# SCH_MAX31865.net
KiCad netlist of a schematic drawn in Altium Designer
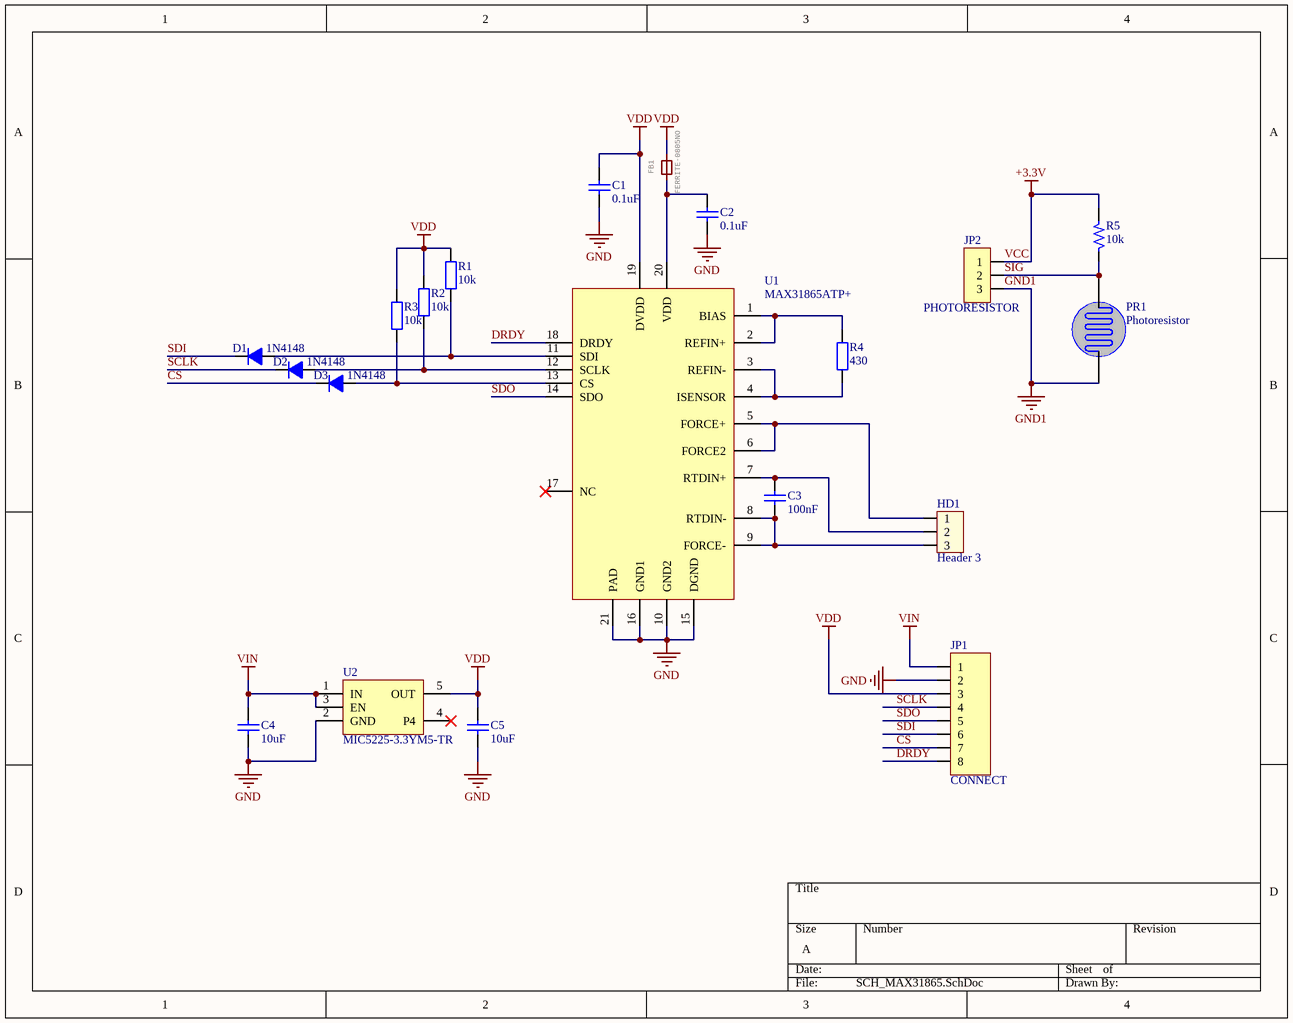
[diagram p0: SCH_MAX31865.SchDoc]

(export (version "E")
  (design (tool "Eeschema 10.0.6"))
  (components
    (comp (ref "C1")
      (value "0.1uF")
      (footprint "tu 0805")
      (description "SMD 0603")
      (libsource (lib "Altium_Lib_by_KhueNguyenCreator") (part "Tu 0805 101 50V 20%"))
    )
    (comp (ref "C2")
      (value "0.1uF")
      (footprint "tu 0805")
      (description "SMD 0603")
      (libsource (lib "Altium_Lib_by_KhueNguyenCreator") (part "Tu 0805 101 50V 20%"))
    )
    (comp (ref "C3")
      (value "100nF")
      (footprint "tu 0805")
      (description "SMD 0603")
      (libsource (lib "Altium_Lib_by_KhueNguyenCreator") (part "Tu 0805 101 50V 20%"))
    )
    (comp (ref "C4")
      (value "10uF")
      (footprint "tu 0805")
      (description "SMD 0603")
      (libsource (lib "Altium_Lib_by_KhueNguyenCreator") (part "Tu 0805 101 50V 20%"))
    )
    (comp (ref "C5")
      (value "10uF")
      (footprint "tu 0805")
      (description "SMD 0603")
      (libsource (lib "Altium_Lib_by_KhueNguyenCreator") (part "Tu 0805 101 50V 20%"))
    )
    (comp (ref "D1")
      (value "1N4148")
      (footprint "SOD523F")
      (description "Diode 1A SMD")
      (libsource (lib "My library altium") (part "Diode  1N4007"))
    )
    (comp (ref "D2")
      (value "1N4148")
      (footprint "SOD523F")
      (description "Diode 1A SMD")
      (libsource (lib "My library altium") (part "Diode  1N4007"))
    )
    (comp (ref "D3")
      (value "1N4148")
      (footprint "SOD523F")
      (description "Diode 1A SMD")
      (libsource (lib "My library altium") (part "Diode  1N4007"))
    )
    (comp (ref "FB1")
      (value "FERRITE-0805NO")
      (footprint "tu 0805")
      (libsource (lib "microbuilder") (part "FERRITE-0805NO"))
    )
    (comp (ref "HD1")
      (value "Header 3")
      (footprint "HED3")
      (description "jumper 1x3")
      (libsource (lib "My library altium") (part "Header 3"))
    )
    (comp (ref "JP1")
      (value "CONNECT")
      (footprint "JP 1x8 DT")
      (description "jumper 1x8")
      (libsource (lib "Altium_Lib_by_KhueNguyenCreator") (part "JP 1x8 2.54 Duc Thang"))
    )
    (comp (ref "JP2")
      (value "PHOTORESISTOR")
      (footprint "JP 1x3 DT")
      (description "Cắm")
      (libsource (lib "Altium_Lib_by_KhueNguyenCreator") (part "JP 1x3 2.54 Duc Thang"))
    )
    (comp (ref "PR1")
      (value "Photoresistor")
      (footprint "CDS")
      (fields (field (name "CREATOR") "Bien Nguyen"))
      (libsource (lib "My library altium") (part "Photoresistor"))
    )
    (comp (ref "R1")
      (value "10k")
      (footprint "tro smd 0805")
      (description "SMD 0603")
      (libsource (lib "Altium_Lib_by_KhueNguyenCreator") (part "Tro 0805 1% 18k"))
    )
    (comp (ref "R2")
      (value "10k")
      (footprint "tro smd 0805")
      (description "SMD 0603")
      (libsource (lib "Altium_Lib_by_KhueNguyenCreator") (part "Tro 0805 1% 18k"))
    )
    (comp (ref "R3")
      (value "10k")
      (footprint "tro smd 0805")
      (description "SMD 0603")
      (libsource (lib "Altium_Lib_by_KhueNguyenCreator") (part "Tro 0805 1% 18k"))
    )
    (comp (ref "R4")
      (value "430")
      (footprint "tro smd 0805")
      (description "SMD 0805")
      (libsource (lib "Altium_Lib_by_KhueNguyenCreator") (part "Tro 0805 1% 18k"))
    )
    (comp (ref "R5")
      (value "10k")
      (footprint "R1/4W")
      (description "Res cắm")
      (libsource (lib "My library altium") (part "Res"))
    )
    (comp (ref "U1")
      (value "MAX31865ATP+")
      (footprint "21-0140_T2055+5_MXM")
      (libsource (lib "MAX31865ATP&plus_plus_") (part "MAX31865ATP+"))
    )
    (comp (ref "U2")
      (value "MIC5225-3.3YM5-TR")
      (footprint "SOT-23-5_M5_MCH")
      (description "No Description Available")
      (libsource (lib "MIC5225-3P3YM5-TR") (part "MIC5225-3.3YM5-TR"))
    )
  )
  (nets
    (net (code "1") (name "+3.3V") (class "Default")
      (node (ref "JP2") (pin "1") (pinfunction "1_1") (pintype "passive"))
      (node (ref "R5") (pin "2") (pinfunction "2_2") (pintype "passive"))
    )
    (net (code "2") (name "/CS") (class "Default")
      (node (ref "D3") (pin "K") (pinfunction "K_K") (pintype "passive"))
      (node (ref "JP1") (pin "7") (pinfunction "7_7") (pintype "passive"))
    )
    (net (code "3") (name "/DRDY") (class "Default")
      (node (ref "JP1") (pin "8") (pinfunction "8_8") (pintype "passive"))
      (node (ref "U1") (pin "18") (pinfunction "DRDY_18") (pintype "passive"))
    )
    (net (code "4") (name "/SCLK") (class "Default")
      (node (ref "D2") (pin "K") (pinfunction "K_K") (pintype "passive"))
      (node (ref "JP1") (pin "4") (pinfunction "4_4") (pintype "passive"))
    )
    (net (code "5") (name "/SDI") (class "Default")
      (node (ref "D1") (pin "K") (pinfunction "K_K") (pintype "passive"))
      (node (ref "JP1") (pin "6") (pinfunction "6_6") (pintype "passive"))
    )
    (net (code "6") (name "/SDO") (class "Default")
      (node (ref "JP1") (pin "5") (pinfunction "5_5") (pintype "passive"))
      (node (ref "U1") (pin "14") (pinfunction "SDO_14") (pintype "passive"))
    )
    (net (code "7") (name "/SIG") (class "Default")
      (node (ref "JP2") (pin "2") (pinfunction "2_2") (pintype "passive"))
      (node (ref "PR1") (pin "2") (pinfunction "2_2") (pintype "passive"))
      (node (ref "R5") (pin "1") (pinfunction "1_1") (pintype "passive"))
    )
    (net (code "8") (name "GND") (class "Default")
      (node (ref "C1") (pin "2") (pinfunction "2_2") (pintype "passive"))
      (node (ref "C2") (pin "2") (pinfunction "2_2") (pintype "passive"))
      (node (ref "C4") (pin "2") (pinfunction "2_2") (pintype "passive"))
      (node (ref "C5") (pin "2") (pinfunction "2_2") (pintype "passive"))
      (node (ref "JP1") (pin "2") (pinfunction "2_2") (pintype "passive"))
      (node (ref "U1") (pin "10") (pinfunction "GND2_10") (pintype "power_in"))
      (node (ref "U1") (pin "15") (pinfunction "DGND_15") (pintype "power_in"))
      (node (ref "U1") (pin "16") (pinfunction "GND1_16") (pintype "power_in"))
      (node (ref "U1") (pin "21") (pinfunction "PAD_21") (pintype "power_in"))
      (node (ref "U2") (pin "2") (pinfunction "GND_2") (pintype "passive"))
    )
    (net (code "9") (name "GND1") (class "Default")
      (node (ref "JP2") (pin "3") (pinfunction "3_3") (pintype "passive"))
      (node (ref "PR1") (pin "1") (pinfunction "1_1") (pintype "passive"))
    )
    (net (code "10") (name "Net-(FB1-P$1)") (class "Default")
      (node (ref "C2") (pin "1") (pinfunction "1_1") (pintype "passive"))
      (node (ref "FB1") (pin "1") (pinfunction "P$1_1") (pintype "passive"))
      (node (ref "U1") (pin "20") (pinfunction "VDD_20") (pintype "power_in"))
    )
    (net (code "11") (name "Net-(U1-BIAS)") (class "Default")
      (node (ref "R4") (pin "2") (pinfunction "2_2") (pintype "passive"))
      (node (ref "U1") (pin "1") (pinfunction "BIAS_1") (pintype "passive"))
      (node (ref "U1") (pin "2") (pinfunction "REFIN+_2") (pintype "passive"))
    )
    (net (code "12") (name "Net-(U1-CS)") (class "Default")
      (node (ref "D3") (pin "A") (pinfunction "A_A") (pintype "passive"))
      (node (ref "R3") (pin "1") (pinfunction "1_1") (pintype "passive"))
      (node (ref "U1") (pin "13") (pinfunction "CS_13") (pintype "passive"))
    )
    (net (code "13") (name "Net-(U1-FORCE+)") (class "Default")
      (node (ref "HD1") (pin "1") (pinfunction "1_1") (pintype "passive"))
      (node (ref "U1") (pin "5") (pinfunction "FORCE+_5") (pintype "passive"))
      (node (ref "U1") (pin "6") (pinfunction "FORCE2_6") (pintype "passive"))
    )
    (net (code "14") (name "Net-(U1-FORCE-)") (class "Default")
      (node (ref "C3") (pin "2") (pinfunction "2_2") (pintype "passive"))
      (node (ref "HD1") (pin "3") (pinfunction "3_3") (pintype "passive"))
      (node (ref "U1") (pin "8") (pinfunction "RTDIN-_8") (pintype "passive"))
      (node (ref "U1") (pin "9") (pinfunction "FORCE-_9") (pintype "passive"))
    )
    (net (code "15") (name "Net-(U1-ISENSOR)") (class "Default")
      (node (ref "R4") (pin "1") (pinfunction "1_1") (pintype "passive"))
      (node (ref "U1") (pin "3") (pinfunction "REFIN-_3") (pintype "passive"))
      (node (ref "U1") (pin "4") (pinfunction "ISENSOR_4") (pintype "passive"))
    )
    (net (code "16") (name "Net-(U1-RTDIN+)") (class "Default")
      (node (ref "C3") (pin "1") (pinfunction "1_1") (pintype "passive"))
      (node (ref "HD1") (pin "2") (pinfunction "2_2") (pintype "passive"))
      (node (ref "U1") (pin "7") (pinfunction "RTDIN+_7") (pintype "passive"))
    )
    (net (code "17") (name "Net-(U1-SCLK)") (class "Default")
      (node (ref "D2") (pin "A") (pinfunction "A_A") (pintype "passive"))
      (node (ref "R2") (pin "1") (pinfunction "1_1") (pintype "passive"))
      (node (ref "U1") (pin "12") (pinfunction "SCLK_12") (pintype "passive"))
    )
    (net (code "18") (name "Net-(U1-SDI)") (class "Default")
      (node (ref "D1") (pin "A") (pinfunction "A_A") (pintype "passive"))
      (node (ref "R1") (pin "1") (pinfunction "1_1") (pintype "passive"))
      (node (ref "U1") (pin "11") (pinfunction "SDI_11") (pintype "passive"))
    )
    (net (code "19") (name "VDD") (class "Default")
      (node (ref "C1") (pin "1") (pinfunction "1_1") (pintype "passive"))
      (node (ref "C5") (pin "1") (pinfunction "1_1") (pintype "passive"))
      (node (ref "FB1") (pin "2") (pinfunction "P$2_2") (pintype "passive"))
      (node (ref "JP1") (pin "3") (pinfunction "3_3") (pintype "passive"))
      (node (ref "R1") (pin "2") (pinfunction "2_2") (pintype "passive"))
      (node (ref "R2") (pin "2") (pinfunction "2_2") (pintype "passive"))
      (node (ref "R3") (pin "2") (pinfunction "2_2") (pintype "passive"))
      (node (ref "U1") (pin "19") (pinfunction "DVDD_19") (pintype "power_in"))
      (node (ref "U2") (pin "5") (pinfunction "OUT_5") (pintype "passive"))
    )
    (net (code "20") (name "VIN") (class "Default")
      (node (ref "C4") (pin "1") (pinfunction "1_1") (pintype "passive"))
      (node (ref "JP1") (pin "1") (pinfunction "1_1") (pintype "passive"))
      (node (ref "U2") (pin "1") (pinfunction "IN_1") (pintype "passive"))
      (node (ref "U2") (pin "3") (pinfunction "EN_3") (pintype "passive"))
    )
    (net (code "21") (name "unconnected-(U1-NC-Pad17)") (class "Default")
      (node (ref "U1") (pin "17") (pinfunction "NC_17") (pintype "passive+no_connect"))
    )
    (net (code "22") (name "unconnected-(U2-P4-Pad4)") (class "Default")
      (node (ref "U2") (pin "4") (pinfunction "P4_4") (pintype "passive+no_connect"))
    )
  )
)
